# control_unit.net
KiCad netlist of a schematic drawn in EAGLE
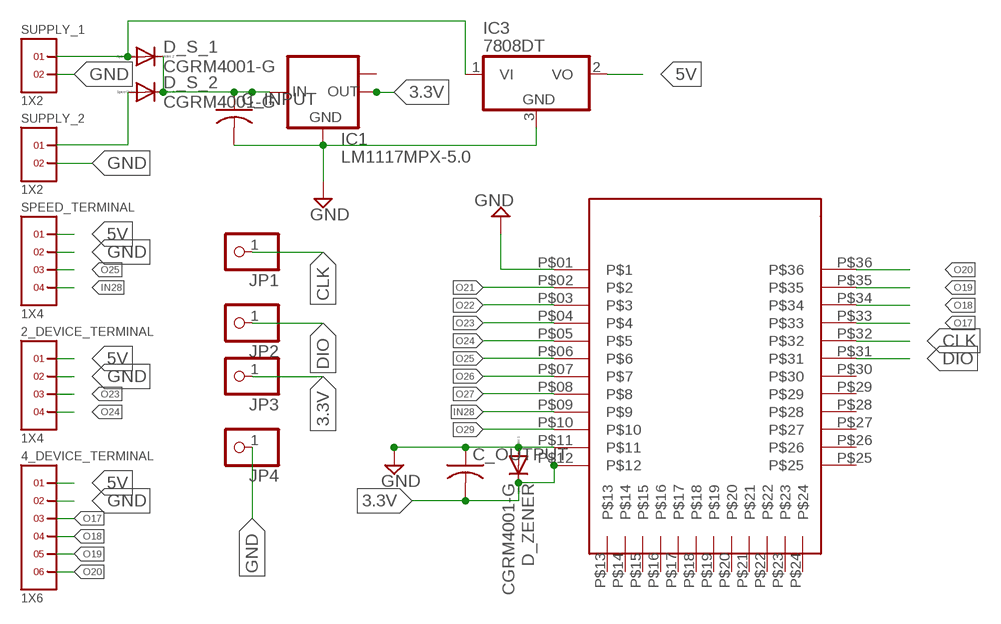
[diagram p0: schematic, sheet 1]

(export (version "E")
  (design (tool "Eeschema 10.0.6"))
  (components
    (comp (ref "2_DEVICE_TERMINAL")
      (value "1X4")
      (footprint "eagle-import:1X4")
      (libsource (lib "eagle-import") (part "1X4"))
    )
    (comp (ref "4_DEVICE_TERMINAL")
      (value "1X6")
      (footprint "eagle-import:1X6")
      (libsource (lib "eagle-import") (part "1X6"))
    )
    (comp (ref "C_INPUT")
      (value "C-USC1206")
      (footprint "eagle-import:C1206")
      (libsource (lib "eagle-import") (part "C-USC1206"))
    )
    (comp (ref "C_OUTPUT")
      (value "C-USC1206")
      (footprint "eagle-import:C1206")
      (libsource (lib "eagle-import") (part "C-USC1206"))
    )
    (comp (ref "D_S_1")
      (value "CGRM4001-G")
      (footprint "eagle-import:SOD-123_MINI-SMA")
      (libsource (lib "eagle-import") (part "CGRM400-G1"))
    )
    (comp (ref "D_S_2")
      (value "CGRM4001-G")
      (footprint "eagle-import:SOD-123_MINI-SMA")
      (libsource (lib "eagle-import") (part "CGRM400-G1"))
    )
    (comp (ref "D_ZENER")
      (value "CGRM4001-G")
      (footprint "eagle-import:SOD-123_MINI-SMA")
      (libsource (lib "eagle-import") (part "CGRM400-G1"))
    )
    (comp (ref "IC1")
      (value "LM1117MPX-5.0")
      (footprint "eagle-import:SOT223")
      (libsource (lib "eagle-import") (part "LM1117MPX-5.0"))
    )
    (comp (ref "IC3")
      (value "7808DT")
      (footprint "eagle-import:TO252")
      (libsource (lib "eagle-import") (part "78DT08"))
    )
    (comp (ref "JP1")
      (value "PINHD-1X1")
      (footprint "eagle-import:1X01")
      (libsource (lib "eagle-import") (part "PINHD-1X1"))
    )
    (comp (ref "JP2")
      (value "PINHD-1X1")
      (footprint "eagle-import:1X01")
      (libsource (lib "eagle-import") (part "PINHD-1X1"))
    )
    (comp (ref "JP3")
      (value "PINHD-1X1")
      (footprint "eagle-import:1X01")
      (libsource (lib "eagle-import") (part "PINHD-1X1"))
    )
    (comp (ref "JP4")
      (value "PINHD-1X1")
      (footprint "eagle-import:1X01")
      (libsource (lib "eagle-import") (part "PINHD-1X1"))
    )
    (comp (ref "SPEED_TERMINAL")
      (value "1X4")
      (footprint "eagle-import:1X4")
      (libsource (lib "eagle-import") (part "1X4"))
    )
    (comp (ref "SUPPLY_1")
      (value "1X2")
      (footprint "eagle-import:1X2")
      (libsource (lib "eagle-import") (part "1X2"))
    )
    (comp (ref "SUPPLY_2")
      (value "1X2")
      (footprint "eagle-import:1X2")
      (libsource (lib "eagle-import") (part "1X2"))
    )
    (comp (ref "U$1")
      (value "HZX_MODULE")
      (footprint "eagle-import:SMD_PAD_VERSION")
      (fields (field (name "AUTHOR") "Agam"))
      (libsource (lib "eagle-import") (part "HZX_MODULE"))
    )
  )
  (nets
    (net (code "1") (name "3.3V") (class "Default")
      (node (ref "C_OUTPUT") (pin "2") (pinfunction "2_2") (pintype "passive"))
      (node (ref "D_ZENER") (pin "C") (pinfunction "C_C") (pintype "passive"))
      (node (ref "IC1") (pin "2") (pinfunction "OUT_2") (pintype "passive"))
      (node (ref "JP3") (pin "1") (pinfunction "1_1") (pintype "passive"))
      (node (ref "U$1") (pin "P$12") (pinfunction "P$12_P$12") (pintype "bidirectional"))
    )
    (net (code "2") (name "5V") (class "Default")
      (node (ref "2_DEVICE_TERMINAL") (pin "1") (pinfunction "1_1") (pintype "bidirectional"))
      (node (ref "4_DEVICE_TERMINAL") (pin "1") (pinfunction "1_1") (pintype "bidirectional"))
      (node (ref "IC3") (pin "2") (pinfunction "VO_2") (pintype "passive"))
      (node (ref "SPEED_TERMINAL") (pin "1") (pinfunction "1_1") (pintype "bidirectional"))
    )
    (net (code "3") (name "CLK") (class "Default")
      (node (ref "JP1") (pin "1") (pinfunction "1_1") (pintype "passive"))
      (node (ref "U$1") (pin "P$32") (pinfunction "P$32_P$32") (pintype "bidirectional"))
    )
    (net (code "4") (name "DIO") (class "Default")
      (node (ref "JP2") (pin "1") (pinfunction "1_1") (pintype "passive"))
      (node (ref "U$1") (pin "P$31") (pinfunction "P$31_P$31") (pintype "bidirectional"))
    )
    (net (code "5") (name "GND") (class "Default")
      (node (ref "2_DEVICE_TERMINAL") (pin "2") (pinfunction "2_2") (pintype "bidirectional"))
      (node (ref "4_DEVICE_TERMINAL") (pin "2") (pinfunction "2_2") (pintype "bidirectional"))
      (node (ref "C_INPUT") (pin "2") (pinfunction "2_2") (pintype "passive"))
      (node (ref "C_OUTPUT") (pin "1") (pinfunction "1_1") (pintype "passive"))
      (node (ref "D_ZENER") (pin "A") (pinfunction "A_A") (pintype "passive"))
      (node (ref "IC1") (pin "1") (pinfunction "GND_1") (pintype "input"))
      (node (ref "IC3") (pin "3") (pinfunction "GND_3") (pintype "passive"))
      (node (ref "JP4") (pin "1") (pinfunction "1_1") (pintype "passive"))
      (node (ref "SPEED_TERMINAL") (pin "2") (pinfunction "2_2") (pintype "bidirectional"))
      (node (ref "SUPPLY_1") (pin "2") (pinfunction "2_2") (pintype "bidirectional"))
      (node (ref "SUPPLY_2") (pin "2") (pinfunction "2_2") (pintype "bidirectional"))
      (node (ref "U$1") (pin "P$01") (pinfunction "P$1_P$01") (pintype "bidirectional"))
      (node (ref "U$1") (pin "P$11") (pinfunction "P$11_P$11") (pintype "bidirectional"))
    )
    (net (code "6") (name "IN28") (class "Default")
      (node (ref "SPEED_TERMINAL") (pin "4") (pinfunction "4_4") (pintype "bidirectional"))
      (node (ref "U$1") (pin "P$09") (pinfunction "P$9_P$09") (pintype "bidirectional"))
    )
    (net (code "7") (name "Net-(D_S_2-PadA)") (class "Default")
      (node (ref "D_S_2") (pin "A") (pinfunction "A_A") (pintype "passive"))
      (node (ref "SUPPLY_2") (pin "1") (pinfunction "1_1") (pintype "bidirectional"))
    )
    (net (code "8") (name "Net-(IC1-IN)") (class "Default")
      (node (ref "C_INPUT") (pin "1") (pinfunction "1_1") (pintype "passive"))
      (node (ref "D_S_1") (pin "C") (pinfunction "C_C") (pintype "passive"))
      (node (ref "D_S_2") (pin "C") (pinfunction "C_C") (pintype "passive"))
      (node (ref "IC1") (pin "3") (pinfunction "IN_3") (pintype "input"))
    )
    (net (code "9") (name "Net-(IC3-VI)") (class "Default")
      (node (ref "D_S_1") (pin "A") (pinfunction "A_A") (pintype "passive"))
      (node (ref "IC3") (pin "1") (pinfunction "VI_1") (pintype "input"))
      (node (ref "SUPPLY_1") (pin "1") (pinfunction "1_1") (pintype "bidirectional"))
    )
    (net (code "10") (name "O17") (class "Default")
      (node (ref "4_DEVICE_TERMINAL") (pin "3") (pinfunction "3_3") (pintype "bidirectional"))
      (node (ref "U$1") (pin "P$33") (pinfunction "P$33_P$33") (pintype "bidirectional"))
    )
    (net (code "11") (name "O18") (class "Default")
      (node (ref "4_DEVICE_TERMINAL") (pin "4") (pinfunction "4_4") (pintype "bidirectional"))
      (node (ref "U$1") (pin "P$34") (pinfunction "P$34_P$34") (pintype "bidirectional"))
    )
    (net (code "12") (name "O19") (class "Default")
      (node (ref "4_DEVICE_TERMINAL") (pin "5") (pinfunction "5_5") (pintype "bidirectional"))
      (node (ref "U$1") (pin "P$35") (pinfunction "P$35_P$35") (pintype "bidirectional"))
    )
    (net (code "13") (name "O20") (class "Default")
      (node (ref "4_DEVICE_TERMINAL") (pin "6") (pinfunction "6_6") (pintype "bidirectional"))
      (node (ref "U$1") (pin "P$36") (pinfunction "P$36_P$36") (pintype "bidirectional"))
    )
    (net (code "14") (name "O21") (class "Default")
      (node (ref "U$1") (pin "P$02") (pinfunction "P$2_P$02") (pintype "bidirectional"))
    )
    (net (code "15") (name "O22") (class "Default")
      (node (ref "U$1") (pin "P$03") (pinfunction "P$3_P$03") (pintype "bidirectional"))
    )
    (net (code "16") (name "O23") (class "Default")
      (node (ref "2_DEVICE_TERMINAL") (pin "3") (pinfunction "3_3") (pintype "bidirectional"))
      (node (ref "U$1") (pin "P$04") (pinfunction "P$4_P$04") (pintype "bidirectional"))
    )
    (net (code "17") (name "O24") (class "Default")
      (node (ref "2_DEVICE_TERMINAL") (pin "4") (pinfunction "4_4") (pintype "bidirectional"))
      (node (ref "U$1") (pin "P$05") (pinfunction "P$5_P$05") (pintype "bidirectional"))
    )
    (net (code "18") (name "O25") (class "Default")
      (node (ref "SPEED_TERMINAL") (pin "3") (pinfunction "3_3") (pintype "bidirectional"))
      (node (ref "U$1") (pin "P$06") (pinfunction "P$6_P$06") (pintype "bidirectional"))
    )
    (net (code "19") (name "O26") (class "Default")
      (node (ref "U$1") (pin "P$07") (pinfunction "P$7_P$07") (pintype "bidirectional"))
    )
    (net (code "20") (name "O27") (class "Default")
      (node (ref "U$1") (pin "P$08") (pinfunction "P$8_P$08") (pintype "bidirectional"))
    )
    (net (code "21") (name "O29") (class "Default")
      (node (ref "U$1") (pin "P$10") (pinfunction "P$10_P$10") (pintype "bidirectional"))
    )
    (net (code "22") (name "unconnected-(IC1-OUT1-PadTAB)") (class "Default")
      (node (ref "IC1") (pin "TAB") (pinfunction "OUT1_TAB") (pintype "passive"))
    )
    (net (code "23") (name "unconnected-(U$1-PadP$13)") (class "Default")
      (node (ref "U$1") (pin "P$13") (pinfunction "P$13_P$13") (pintype "bidirectional"))
    )
    (net (code "24") (name "unconnected-(U$1-PadP$14)") (class "Default")
      (node (ref "U$1") (pin "P$14") (pinfunction "P$14_P$14") (pintype "bidirectional"))
    )
    (net (code "25") (name "unconnected-(U$1-PadP$15)") (class "Default")
      (node (ref "U$1") (pin "P$15") (pinfunction "P$15_P$15") (pintype "bidirectional"))
    )
    (net (code "26") (name "unconnected-(U$1-PadP$16)") (class "Default")
      (node (ref "U$1") (pin "P$16") (pinfunction "P$16_P$16") (pintype "bidirectional"))
    )
    (net (code "27") (name "unconnected-(U$1-PadP$17)") (class "Default")
      (node (ref "U$1") (pin "P$17") (pinfunction "P$17_P$17") (pintype "bidirectional"))
    )
    (net (code "28") (name "unconnected-(U$1-PadP$18)") (class "Default")
      (node (ref "U$1") (pin "P$18") (pinfunction "P$18_P$18") (pintype "bidirectional"))
    )
    (net (code "29") (name "unconnected-(U$1-PadP$19)") (class "Default")
      (node (ref "U$1") (pin "P$19") (pinfunction "P$19_P$19") (pintype "bidirectional"))
    )
    (net (code "30") (name "unconnected-(U$1-PadP$20)") (class "Default")
      (node (ref "U$1") (pin "P$20") (pinfunction "P$20_P$20") (pintype "bidirectional"))
    )
    (net (code "31") (name "unconnected-(U$1-PadP$21)") (class "Default")
      (node (ref "U$1") (pin "P$21") (pinfunction "P$21_P$21") (pintype "bidirectional"))
    )
    (net (code "32") (name "unconnected-(U$1-PadP$22)") (class "Default")
      (node (ref "U$1") (pin "P$22") (pinfunction "P$22_P$22") (pintype "bidirectional"))
    )
    (net (code "33") (name "unconnected-(U$1-PadP$23)") (class "Default")
      (node (ref "U$1") (pin "P$23") (pinfunction "P$23_P$23") (pintype "bidirectional"))
    )
    (net (code "34") (name "unconnected-(U$1-PadP$24)") (class "Default")
      (node (ref "U$1") (pin "P$24") (pinfunction "P$24_P$24") (pintype "bidirectional"))
    )
    (net (code "35") (name "unconnected-(U$1-PadP$25)") (class "Default")
      (node (ref "U$1") (pin "P$25") (pinfunction "P$25_P$25") (pintype "bidirectional"))
    )
    (net (code "36") (name "unconnected-(U$1-PadP$26)") (class "Default")
      (node (ref "U$1") (pin "P$26") (pinfunction "P$26_P$26") (pintype "bidirectional"))
    )
    (net (code "37") (name "unconnected-(U$1-PadP$27)") (class "Default")
      (node (ref "U$1") (pin "P$27") (pinfunction "P$27_P$27") (pintype "bidirectional"))
    )
    (net (code "38") (name "unconnected-(U$1-PadP$28)") (class "Default")
      (node (ref "U$1") (pin "P$28") (pinfunction "P$28_P$28") (pintype "bidirectional"))
    )
    (net (code "39") (name "unconnected-(U$1-PadP$29)") (class "Default")
      (node (ref "U$1") (pin "P$29") (pinfunction "P$29_P$29") (pintype "bidirectional"))
    )
    (net (code "40") (name "unconnected-(U$1-PadP$30)") (class "Default")
      (node (ref "U$1") (pin "P$30") (pinfunction "P$30_P$30") (pintype "bidirectional"))
    )
  )
)
